# preliminary-board.net
KiCad netlist of a schematic drawn in EAGLE
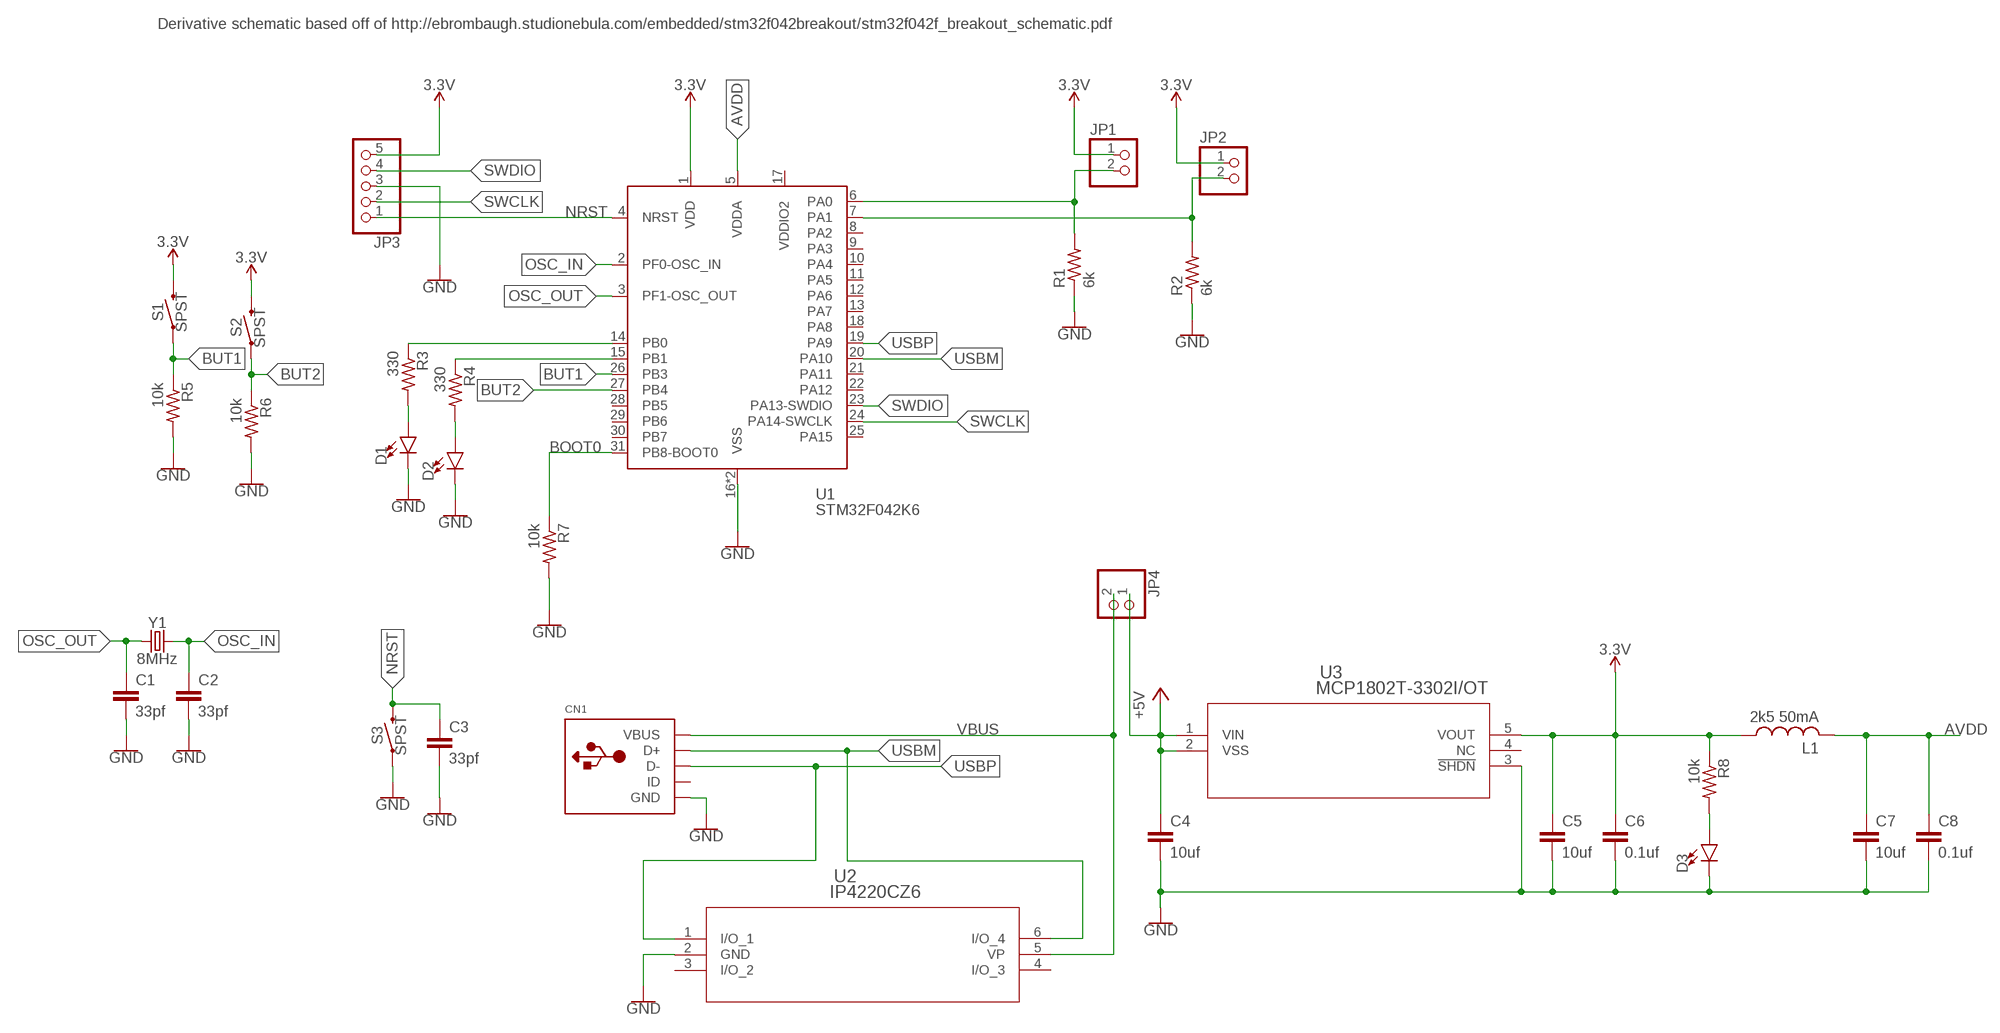
[diagram p0: schematic, sheet 1]

(export (version "E")
  (design (tool "Eeschema 10.0.6"))
  (components
    (comp (ref "C1")
      (value "33pf")
      (footprint "eagle-import:C0805")
      (libsource (lib "eagle-import") (part "C-EUC0805"))
    )
    (comp (ref "C2")
      (value "33pf")
      (footprint "eagle-import:C0805")
      (libsource (lib "eagle-import") (part "C-EUC0805"))
    )
    (comp (ref "C3")
      (value "33pf")
      (footprint "eagle-import:C0805")
      (libsource (lib "eagle-import") (part "C-EUC0805"))
    )
    (comp (ref "C4")
      (value "10uf")
      (footprint "eagle-import:C0805")
      (libsource (lib "eagle-import") (part "C-EUC0805"))
    )
    (comp (ref "C5")
      (value "10uf")
      (footprint "eagle-import:C0805")
      (libsource (lib "eagle-import") (part "C-EUC0805"))
    )
    (comp (ref "C6")
      (value "0.1uf")
      (footprint "eagle-import:C0805")
      (libsource (lib "eagle-import") (part "C-EUC0805"))
    )
    (comp (ref "C7")
      (value "10uf")
      (footprint "eagle-import:C0805")
      (libsource (lib "eagle-import") (part "C-EUC0805"))
    )
    (comp (ref "C8")
      (value "0.1uf")
      (footprint "eagle-import:C0805")
      (libsource (lib "eagle-import") (part "C-EUC0805"))
    )
    (comp (ref "CN1")
      (value "USBMOLEX")
      (footprint "eagle-import:USB-MINIB-THM-MOLEX")
      (libsource (lib "eagle-import") (part "USBMOLEX"))
    )
    (comp (ref "D1")
      (value "LED10MM")
      (footprint "eagle-import:LED_10MM")
      (libsource (lib "eagle-import") (part "LED10MM"))
    )
    (comp (ref "D2")
      (value "LED10MM")
      (footprint "eagle-import:LED_10MM")
      (libsource (lib "eagle-import") (part "LED10MM"))
    )
    (comp (ref "D3")
      (value "LED10MM")
      (footprint "eagle-import:LED_10MM")
      (libsource (lib "eagle-import") (part "LED10MM"))
    )
    (comp (ref "JP1")
      (value "PINHD-1X2")
      (footprint "eagle-import:1X02")
      (libsource (lib "eagle-import") (part "PINHD-1X2"))
    )
    (comp (ref "JP2")
      (value "PINHD-1X2")
      (footprint "eagle-import:1X02")
      (libsource (lib "eagle-import") (part "PINHD-1X2"))
    )
    (comp (ref "JP3")
      (value "PINHD-1X5")
      (footprint "eagle-import:1X05")
      (libsource (lib "eagle-import") (part "PINHD-1X5"))
    )
    (comp (ref "JP4")
      (value "PINHD-1X2")
      (footprint "eagle-import:1X02")
      (libsource (lib "eagle-import") (part "PINHD-1X2"))
    )
    (comp (ref "L1")
      (value "2k5 50mA")
      (footprint "eagle-import:L3216C")
      (libsource (lib "eagle-import") (part "L-USL3216C"))
    )
    (comp (ref "R1")
      (value "6k")
      (footprint "eagle-import:R0805")
      (libsource (lib "eagle-import") (part "R-US_R0805"))
    )
    (comp (ref "R2")
      (value "6k")
      (footprint "eagle-import:R0805")
      (libsource (lib "eagle-import") (part "R-US_R0805"))
    )
    (comp (ref "R3")
      (value "330")
      (footprint "eagle-import:R0805")
      (libsource (lib "eagle-import") (part "R-US_R0805"))
    )
    (comp (ref "R4")
      (value "330")
      (footprint "eagle-import:R0805")
      (libsource (lib "eagle-import") (part "R-US_R0805"))
    )
    (comp (ref "R5")
      (value "10k")
      (footprint "eagle-import:R0805")
      (libsource (lib "eagle-import") (part "R-US_R0805"))
    )
    (comp (ref "R6")
      (value "10k")
      (footprint "eagle-import:R0805")
      (libsource (lib "eagle-import") (part "R-US_R0805"))
    )
    (comp (ref "R7")
      (value "10k")
      (footprint "eagle-import:R0805")
      (libsource (lib "eagle-import") (part "R-US_R0805"))
    )
    (comp (ref "R8")
      (value "10k")
      (footprint "eagle-import:R0805")
      (libsource (lib "eagle-import") (part "R-US_R0805"))
    )
    (comp (ref "S1")
      (value "SPST")
      (footprint "eagle-import:TACTILE_SWITCH_PTH_6.0MM")
      (libsource (lib "eagle-import") (part "MOMENTARY-SWITCH-SPST-PTH-6.0MM"))
    )
    (comp (ref "S2")
      (value "SPST")
      (footprint "eagle-import:TACTILE_SWITCH_PTH_6.0MM")
      (libsource (lib "eagle-import") (part "MOMENTARY-SWITCH-SPST-PTH-6.0MM"))
    )
    (comp (ref "S3")
      (value "SPST")
      (footprint "eagle-import:TACTILE_SWITCH_PTH_6.0MM")
      (libsource (lib "eagle-import") (part "MOMENTARY-SWITCH-SPST-PTH-6.0MM"))
    )
    (comp (ref "U1")
      (value "STM32F042K6")
      (footprint "eagle-import:QFP32-7X7")
      (libsource (lib "eagle-import") (part "STM32F042K6"))
    )
    (comp (ref "U2")
      (value "IP4220CZ6")
      (footprint "eagle-import:SOT457")
      (libsource (lib "eagle-import") (part "IP4220CZ6"))
    )
    (comp (ref "U3")
      (value "MCP1802T-3302I/OT")
      (footprint "eagle-import:SOT-23-5_MC")
      (fields (field (name "MANUFACTURER_PART_NUMBER") "MCP1802T3302IOT"))
      (libsource (lib "eagle-import") (part "MCP1802T-3302I/OT"))
    )
    (comp (ref "Y1")
      (value "8MHz")
      (footprint "eagle-import:HC49UP")
      (libsource (lib "eagle-import") (part "CRYSTAL-8MHZSMD-HC49UP"))
    )
  )
  (nets
    (net (code "1") (name "+5V") (class "Default")
      (node (ref "C4") (pin "1") (pinfunction "1_1") (pintype "passive"))
      (node (ref "JP4") (pin "1") (pinfunction "1_1") (pintype "passive"))
      (node (ref "U3") (pin "1") (pinfunction "VIN_1") (pintype "passive"))
      (node (ref "U3") (pin "2") (pinfunction "VSS_2") (pintype "passive"))
    )
    (net (code "2") (name "/BOOT0") (class "Default")
      (node (ref "R7") (pin "1") (pinfunction "1_1") (pintype "passive"))
      (node (ref "U1") (pin "31") (pinfunction "PB8-BOOT0_31") (pintype "bidirectional"))
    )
    (net (code "3") (name "/VBUS") (class "Default")
      (node (ref "CN1") (pin "VBUS") (pinfunction "VBUS_VBUS") (pintype "power_in"))
      (node (ref "JP4") (pin "2") (pinfunction "2_2") (pintype "passive"))
      (node (ref "U2") (pin "5") (pinfunction "VP_5") (pintype "passive"))
    )
    (net (code "4") (name "/VDDIO2") (class "Default")
      (node (ref "U1") (pin "17") (pinfunction "VDDIO2_17") (pintype "power_in"))
    )
    (net (code "5") (name "3.3V") (class "Default")
      (node (ref "C5") (pin "1") (pinfunction "1_1") (pintype "passive"))
      (node (ref "C6") (pin "1") (pinfunction "1_1") (pintype "passive"))
      (node (ref "JP1") (pin "1") (pinfunction "1_1") (pintype "passive"))
      (node (ref "JP2") (pin "1") (pinfunction "1_1") (pintype "passive"))
      (node (ref "JP3") (pin "5") (pinfunction "5_5") (pintype "passive"))
      (node (ref "L1") (pin "1") (pinfunction "1_1") (pintype "passive"))
      (node (ref "R8") (pin "1") (pinfunction "1_1") (pintype "passive"))
      (node (ref "S1") (pin "3") (pinfunction "2_3") (pintype "passive"))
      (node (ref "S2") (pin "3") (pinfunction "2_3") (pintype "passive"))
      (node (ref "U1") (pin "1") (pinfunction "VDD_1") (pintype "power_in"))
      (node (ref "U3") (pin "5") (pinfunction "VOUT_5") (pintype "passive"))
    )
    (net (code "6") (name "AVDD") (class "Default")
      (node (ref "C7") (pin "1") (pinfunction "1_1") (pintype "passive"))
      (node (ref "C8") (pin "1") (pinfunction "1_1") (pintype "passive"))
      (node (ref "L1") (pin "2") (pinfunction "2_2") (pintype "passive"))
      (node (ref "U1") (pin "5") (pinfunction "VDDA_5") (pintype "power_in"))
    )
    (net (code "7") (name "BUT1") (class "Default")
      (node (ref "R5") (pin "1") (pinfunction "1_1") (pintype "passive"))
      (node (ref "S1") (pin "1") (pinfunction "1_1") (pintype "passive"))
      (node (ref "U1") (pin "26") (pinfunction "PB3_26") (pintype "bidirectional"))
    )
    (net (code "8") (name "BUT2") (class "Default")
      (node (ref "R6") (pin "1") (pinfunction "1_1") (pintype "passive"))
      (node (ref "S2") (pin "1") (pinfunction "1_1") (pintype "passive"))
      (node (ref "U1") (pin "27") (pinfunction "PB4_27") (pintype "bidirectional"))
    )
    (net (code "9") (name "GND") (class "Default")
      (node (ref "C1") (pin "2") (pinfunction "2_2") (pintype "passive"))
      (node (ref "C2") (pin "2") (pinfunction "2_2") (pintype "passive"))
      (node (ref "C3") (pin "2") (pinfunction "2_2") (pintype "passive"))
      (node (ref "C4") (pin "2") (pinfunction "2_2") (pintype "passive"))
      (node (ref "C5") (pin "2") (pinfunction "2_2") (pintype "passive"))
      (node (ref "C6") (pin "2") (pinfunction "2_2") (pintype "passive"))
      (node (ref "C7") (pin "2") (pinfunction "2_2") (pintype "passive"))
      (node (ref "C8") (pin "2") (pinfunction "2_2") (pintype "passive"))
      (node (ref "CN1") (pin "GND") (pinfunction "GND_GND") (pintype "power_in"))
      (node (ref "D1") (pin "C") (pinfunction "C_C") (pintype "passive"))
      (node (ref "D2") (pin "C") (pinfunction "C_C") (pintype "passive"))
      (node (ref "D3") (pin "C") (pinfunction "C_C") (pintype "passive"))
      (node (ref "JP3") (pin "3") (pinfunction "3_3") (pintype "passive"))
      (node (ref "R1") (pin "1") (pinfunction "1_1") (pintype "passive"))
      (node (ref "R2") (pin "1") (pinfunction "1_1") (pintype "passive"))
      (node (ref "R5") (pin "2") (pinfunction "2_2") (pintype "passive"))
      (node (ref "R6") (pin "2") (pinfunction "2_2") (pintype "passive"))
      (node (ref "R7") (pin "2") (pinfunction "2_2") (pintype "passive"))
      (node (ref "S3") (pin "1") (pinfunction "1_1") (pintype "passive"))
      (node (ref "U1") (pin "16") (pinfunction "VSS_16") (pintype "power_in"))
      (node (ref "U1") (pin "32") (pinfunction "VSS_32") (pintype "power_in"))
      (node (ref "U2") (pin "2") (pinfunction "GND_2") (pintype "passive"))
      (node (ref "U3") (pin "3") (pinfunction "~{SHDN}_3") (pintype "passive"))
    )
    (net (code "10") (name "NRST") (class "Default")
      (node (ref "C3") (pin "1") (pinfunction "1_1") (pintype "passive"))
      (node (ref "JP3") (pin "1") (pinfunction "1_1") (pintype "passive"))
      (node (ref "S3") (pin "3") (pinfunction "2_3") (pintype "passive"))
      (node (ref "U1") (pin "4") (pinfunction "NRST_4") (pintype "bidirectional"))
    )
    (net (code "11") (name "Net-(D1-PadA)") (class "Default")
      (node (ref "D1") (pin "A") (pinfunction "A_A") (pintype "passive"))
      (node (ref "R3") (pin "2") (pinfunction "2_2") (pintype "passive"))
    )
    (net (code "12") (name "Net-(D2-PadA)") (class "Default")
      (node (ref "D2") (pin "A") (pinfunction "A_A") (pintype "passive"))
      (node (ref "R4") (pin "2") (pinfunction "2_2") (pintype "passive"))
    )
    (net (code "13") (name "Net-(D3-PadA)") (class "Default")
      (node (ref "D3") (pin "A") (pinfunction "A_A") (pintype "passive"))
      (node (ref "R8") (pin "2") (pinfunction "2_2") (pintype "passive"))
    )
    (net (code "14") (name "Net-(U1-PA0)") (class "Default")
      (node (ref "JP1") (pin "2") (pinfunction "2_2") (pintype "passive"))
      (node (ref "R1") (pin "2") (pinfunction "2_2") (pintype "passive"))
      (node (ref "U1") (pin "6") (pinfunction "PA0_6") (pintype "bidirectional"))
    )
    (net (code "15") (name "Net-(U1-PA1)") (class "Default")
      (node (ref "JP2") (pin "2") (pinfunction "2_2") (pintype "passive"))
      (node (ref "R2") (pin "2") (pinfunction "2_2") (pintype "passive"))
      (node (ref "U1") (pin "7") (pinfunction "PA1_7") (pintype "bidirectional"))
    )
    (net (code "16") (name "Net-(U1-PB0)") (class "Default")
      (node (ref "R3") (pin "1") (pinfunction "1_1") (pintype "passive"))
      (node (ref "U1") (pin "14") (pinfunction "PB0_14") (pintype "bidirectional"))
    )
    (net (code "17") (name "Net-(U1-PB1)") (class "Default")
      (node (ref "R4") (pin "1") (pinfunction "1_1") (pintype "passive"))
      (node (ref "U1") (pin "15") (pinfunction "PB1_15") (pintype "bidirectional"))
    )
    (net (code "18") (name "OSC_IN") (class "Default")
      (node (ref "C2") (pin "1") (pinfunction "1_1") (pintype "passive"))
      (node (ref "U1") (pin "2") (pinfunction "PF0-OSC_IN_2") (pintype "bidirectional"))
      (node (ref "Y1") (pin "2") (pinfunction "2_2") (pintype "passive"))
    )
    (net (code "19") (name "OSC_OUT") (class "Default")
      (node (ref "C1") (pin "1") (pinfunction "1_1") (pintype "passive"))
      (node (ref "U1") (pin "3") (pinfunction "PF1-OSC_OUT_3") (pintype "bidirectional"))
      (node (ref "Y1") (pin "1") (pinfunction "1_1") (pintype "passive"))
    )
    (net (code "20") (name "SWCLK") (class "Default")
      (node (ref "JP3") (pin "2") (pinfunction "2_2") (pintype "passive"))
      (node (ref "U1") (pin "24") (pinfunction "PA14-SWCLK_24") (pintype "bidirectional"))
    )
    (net (code "21") (name "SWDIO") (class "Default")
      (node (ref "JP3") (pin "4") (pinfunction "4_4") (pintype "passive"))
      (node (ref "U1") (pin "23") (pinfunction "PA13-SWDIO_23") (pintype "bidirectional"))
    )
    (net (code "22") (name "USBM") (class "Default")
      (node (ref "CN1") (pin "D+") (pinfunction "D+_D+") (pintype "bidirectional"))
      (node (ref "U1") (pin "20") (pinfunction "PA10_20") (pintype "bidirectional"))
      (node (ref "U2") (pin "6") (pinfunction "I/O_4_6") (pintype "passive"))
    )
    (net (code "23") (name "USBP") (class "Default")
      (node (ref "CN1") (pin "D-") (pinfunction "D-_D-") (pintype "bidirectional"))
      (node (ref "U1") (pin "19") (pinfunction "PA9_19") (pintype "bidirectional"))
      (node (ref "U2") (pin "1") (pinfunction "I/O_1_1") (pintype "passive"))
    )
    (net (code "24") (name "unconnected-(CN1-PadID)") (class "Default")
      (node (ref "CN1") (pin "ID") (pinfunction "ID_ID") (pintype "bidirectional"))
    )
    (net (code "25") (name "unconnected-(U1-PA2-Pad8)") (class "Default")
      (node (ref "U1") (pin "8") (pinfunction "PA2_8") (pintype "bidirectional"))
    )
    (net (code "26") (name "unconnected-(U1-PA3-Pad9)") (class "Default")
      (node (ref "U1") (pin "9") (pinfunction "PA3_9") (pintype "bidirectional"))
    )
    (net (code "27") (name "unconnected-(U1-PA4-Pad10)") (class "Default")
      (node (ref "U1") (pin "10") (pinfunction "PA4_10") (pintype "bidirectional"))
    )
    (net (code "28") (name "unconnected-(U1-PA5-Pad11)") (class "Default")
      (node (ref "U1") (pin "11") (pinfunction "PA5_11") (pintype "bidirectional"))
    )
    (net (code "29") (name "unconnected-(U1-PA6-Pad12)") (class "Default")
      (node (ref "U1") (pin "12") (pinfunction "PA6_12") (pintype "bidirectional"))
    )
    (net (code "30") (name "unconnected-(U1-PA7-Pad13)") (class "Default")
      (node (ref "U1") (pin "13") (pinfunction "PA7_13") (pintype "bidirectional"))
    )
    (net (code "31") (name "unconnected-(U1-PA8-Pad18)") (class "Default")
      (node (ref "U1") (pin "18") (pinfunction "PA8_18") (pintype "bidirectional"))
    )
    (net (code "32") (name "unconnected-(U1-PA11-Pad21)") (class "Default")
      (node (ref "U1") (pin "21") (pinfunction "PA11_21") (pintype "bidirectional"))
    )
    (net (code "33") (name "unconnected-(U1-PA12-Pad22)") (class "Default")
      (node (ref "U1") (pin "22") (pinfunction "PA12_22") (pintype "bidirectional"))
    )
    (net (code "34") (name "unconnected-(U1-PA15-Pad25)") (class "Default")
      (node (ref "U1") (pin "25") (pinfunction "PA15_25") (pintype "bidirectional"))
    )
    (net (code "35") (name "unconnected-(U1-PB5-Pad28)") (class "Default")
      (node (ref "U1") (pin "28") (pinfunction "PB5_28") (pintype "bidirectional"))
    )
    (net (code "36") (name "unconnected-(U1-PB6-Pad29)") (class "Default")
      (node (ref "U1") (pin "29") (pinfunction "PB6_29") (pintype "bidirectional"))
    )
    (net (code "37") (name "unconnected-(U1-PB7-Pad30)") (class "Default")
      (node (ref "U1") (pin "30") (pinfunction "PB7_30") (pintype "bidirectional"))
    )
    (net (code "38") (name "unconnected-(U2-I{slash}O_2-Pad3)") (class "Default")
      (node (ref "U2") (pin "3") (pinfunction "I/O_2_3") (pintype "passive"))
    )
    (net (code "39") (name "unconnected-(U2-I{slash}O_3-Pad4)") (class "Default")
      (node (ref "U2") (pin "4") (pinfunction "I/O_3_4") (pintype "passive"))
    )
    (net (code "40") (name "unconnected-(U3-NC-Pad4)") (class "Default")
      (node (ref "U3") (pin "4") (pinfunction "NC_4") (pintype "passive"))
    )
  )
)
